# V1_0.net
KiCad netlist of a schematic drawn in EasyEDA Pro
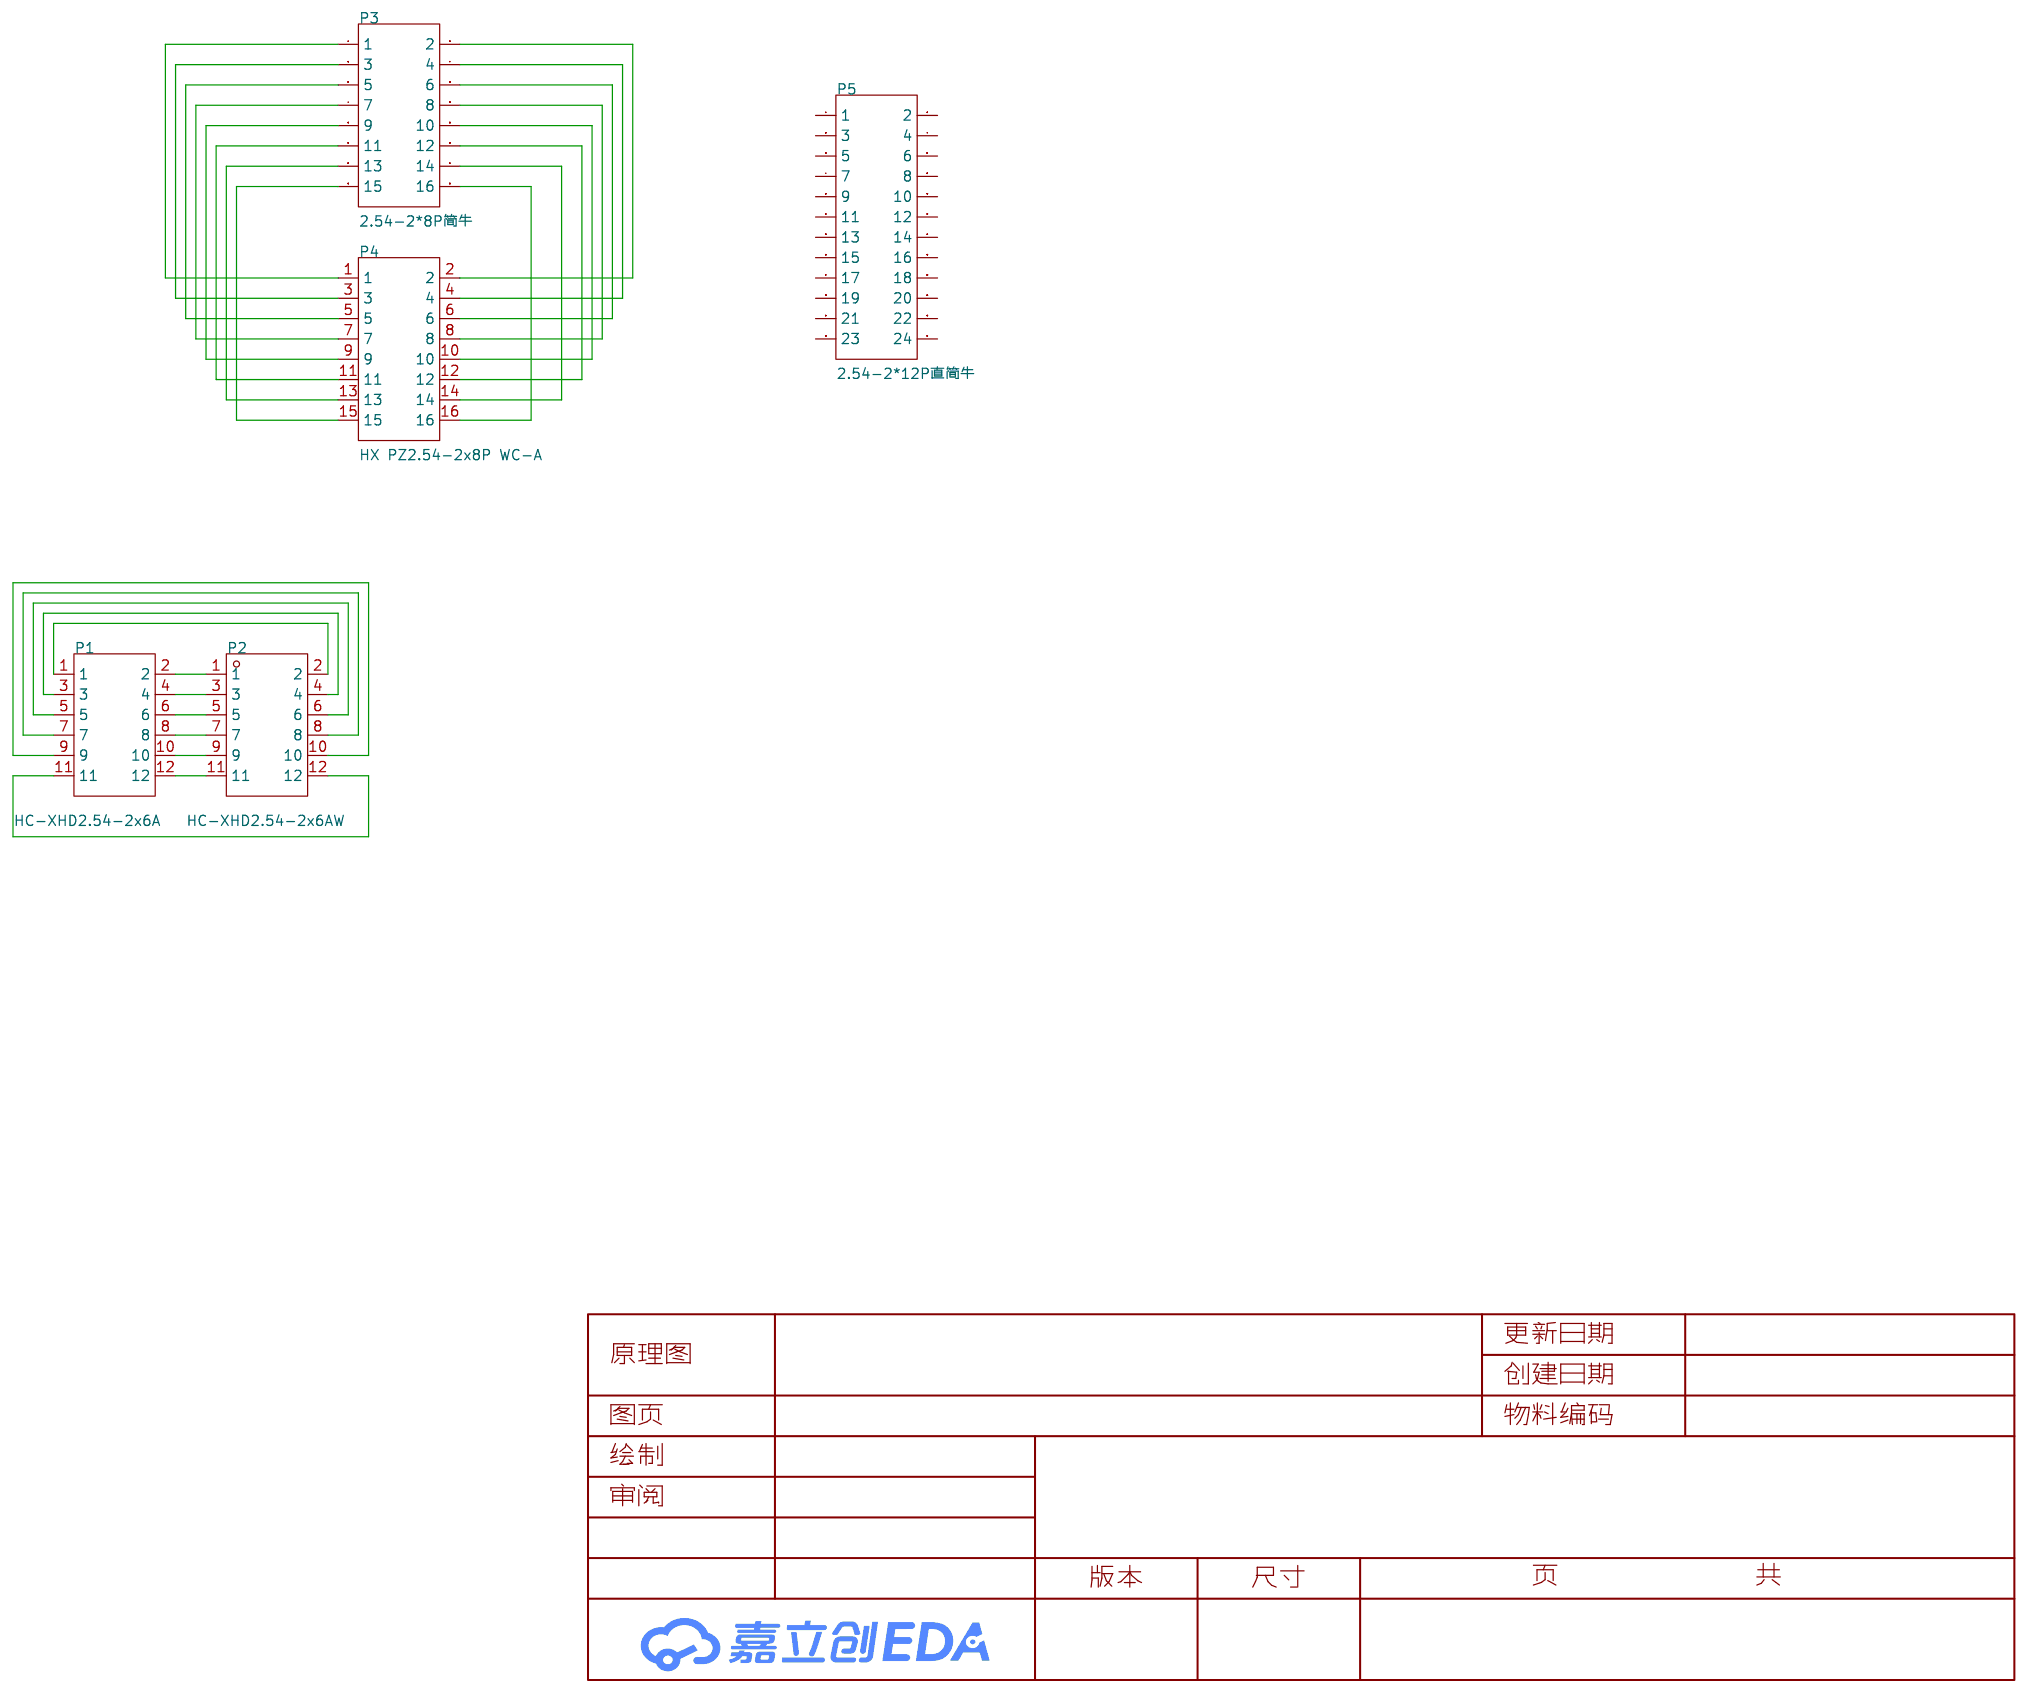
[diagram p0: schematic sheet]

(export (version "E")
  (design (tool "Eeschema 10.0.6"))
  (components
    (comp (ref "P1")
      (value "HC-XHD2.54-2x6A")
      (footprint "easyedapro:CONN-TH_12P-P2.50_HC-XHD2.54-2X6A")
      (fields (field (name "Manufacturer") "HC(虹成电子)"))
      (libsource (lib "easyedapro") (part "HC-XHD2.54-2X6A"))
    )
    (comp (ref "P2")
      (value "HC-XHD2.54-2x6AW")
      (footprint "easyedapro:CONN-TH_12P-P2.50_HC-XHD2.54-2X6AW")
      (fields (field (name "Manufacturer") "HC(虹成电子)"))
      (libsource (lib "easyedapro") (part "HC-XHD2.54-2X6AW"))
    )
    (comp (ref "P3")
      (value "2.54-2*8P简牛")
      (footprint "easyedapro:IDC-TH_16P-P2.54_C3406")
      (description "连接器类型:简牛座;间距:2.54mm;结构:2x8P;安装方式:直插;行距:2.54mm;排数:2;每排PIN数:8;触头材质:-;触头镀层:-;")
      (fields (field (name "Manufacturer") "BOOMELE(博穆精密)"))
      (libsource (lib "easyedapro") (part "HDR-IDC-2.54-2X8P"))
    )
    (comp (ref "P4")
      (value "HX PZ2.54-2x8P WC-A")
      (footprint "easyedapro:HDR-TH_16P-P2.54-H-M-R2-C8-S2.54-W12.9-N")
      (fields (field (name "Manufacturer") "hanxia(韩下)"))
      (libsource (lib "easyedapro") (part "HX PZ2.54-2X8P WC-A"))
    )
    (comp (ref "P5")
      (value "2.54-2*12P直简牛")
      (footprint "easyedapro:IDC-TH_24P-P2.54-V-R2-C12-S2.54")
      (fields (field (name "Manufacturer") "BOOMELE(博穆精密)"))
      (libsource (lib "easyedapro") (part "HDR-IDC-2.54-2X12P"))
    )
  )
  (nets
    (net (code "1") (name "Net-(P1-Pad1)") (class "Default")
      (node (ref "P1") (pin "1") (pinfunction "1_1") (pintype "unspecified"))
      (node (ref "P2") (pin "2") (pinfunction "2_2") (pintype "unspecified"))
    )
    (net (code "2") (name "Net-(P1-Pad2)") (class "Default")
      (node (ref "P1") (pin "2") (pinfunction "2_2") (pintype "unspecified"))
      (node (ref "P2") (pin "1") (pinfunction "1_1") (pintype "unspecified"))
    )
    (net (code "3") (name "Net-(P1-Pad3)") (class "Default")
      (node (ref "P1") (pin "3") (pinfunction "3_3") (pintype "unspecified"))
      (node (ref "P2") (pin "4") (pinfunction "4_4") (pintype "unspecified"))
    )
    (net (code "4") (name "Net-(P1-Pad4)") (class "Default")
      (node (ref "P1") (pin "4") (pinfunction "4_4") (pintype "unspecified"))
      (node (ref "P2") (pin "3") (pinfunction "3_3") (pintype "unspecified"))
    )
    (net (code "5") (name "Net-(P1-Pad5)") (class "Default")
      (node (ref "P1") (pin "5") (pinfunction "5_5") (pintype "unspecified"))
      (node (ref "P2") (pin "6") (pinfunction "6_6") (pintype "unspecified"))
    )
    (net (code "6") (name "Net-(P1-Pad6)") (class "Default")
      (node (ref "P1") (pin "6") (pinfunction "6_6") (pintype "unspecified"))
      (node (ref "P2") (pin "5") (pinfunction "5_5") (pintype "unspecified"))
    )
    (net (code "7") (name "Net-(P1-Pad7)") (class "Default")
      (node (ref "P1") (pin "7") (pinfunction "7_7") (pintype "unspecified"))
      (node (ref "P2") (pin "8") (pinfunction "8_8") (pintype "unspecified"))
    )
    (net (code "8") (name "Net-(P1-Pad8)") (class "Default")
      (node (ref "P1") (pin "8") (pinfunction "8_8") (pintype "unspecified"))
      (node (ref "P2") (pin "7") (pinfunction "7_7") (pintype "unspecified"))
    )
    (net (code "9") (name "Net-(P1-Pad9)") (class "Default")
      (node (ref "P1") (pin "9") (pinfunction "9_9") (pintype "unspecified"))
      (node (ref "P2") (pin "10") (pinfunction "10_10") (pintype "unspecified"))
    )
    (net (code "10") (name "Net-(P1-Pad10)") (class "Default")
      (node (ref "P1") (pin "10") (pinfunction "10_10") (pintype "unspecified"))
      (node (ref "P2") (pin "9") (pinfunction "9_9") (pintype "unspecified"))
    )
    (net (code "11") (name "Net-(P1-Pad11)") (class "Default")
      (node (ref "P1") (pin "11") (pinfunction "11_11") (pintype "unspecified"))
      (node (ref "P2") (pin "12") (pinfunction "12_12") (pintype "unspecified"))
    )
    (net (code "12") (name "Net-(P1-Pad12)") (class "Default")
      (node (ref "P1") (pin "12") (pinfunction "12_12") (pintype "unspecified"))
      (node (ref "P2") (pin "11") (pinfunction "11_11") (pintype "unspecified"))
    )
    (net (code "13") (name "Net-(P3-Pad1)") (class "Default")
      (node (ref "P3") (pin "1") (pinfunction "1_1") (pintype "unspecified"))
      (node (ref "P4") (pin "1") (pinfunction "1_1") (pintype "unspecified"))
    )
    (net (code "14") (name "Net-(P3-Pad2)") (class "Default")
      (node (ref "P3") (pin "2") (pinfunction "2_2") (pintype "unspecified"))
      (node (ref "P4") (pin "2") (pinfunction "2_2") (pintype "unspecified"))
    )
    (net (code "15") (name "Net-(P3-Pad3)") (class "Default")
      (node (ref "P3") (pin "3") (pinfunction "3_3") (pintype "unspecified"))
      (node (ref "P4") (pin "3") (pinfunction "3_3") (pintype "unspecified"))
    )
    (net (code "16") (name "Net-(P3-Pad4)") (class "Default")
      (node (ref "P3") (pin "4") (pinfunction "4_4") (pintype "unspecified"))
      (node (ref "P4") (pin "4") (pinfunction "4_4") (pintype "unspecified"))
    )
    (net (code "17") (name "Net-(P3-Pad5)") (class "Default")
      (node (ref "P3") (pin "5") (pinfunction "5_5") (pintype "unspecified"))
      (node (ref "P4") (pin "5") (pinfunction "5_5") (pintype "unspecified"))
    )
    (net (code "18") (name "Net-(P3-Pad6)") (class "Default")
      (node (ref "P3") (pin "6") (pinfunction "6_6") (pintype "unspecified"))
      (node (ref "P4") (pin "6") (pinfunction "6_6") (pintype "unspecified"))
    )
    (net (code "19") (name "Net-(P3-Pad7)") (class "Default")
      (node (ref "P3") (pin "7") (pinfunction "7_7") (pintype "unspecified"))
      (node (ref "P4") (pin "7") (pinfunction "7_7") (pintype "unspecified"))
    )
    (net (code "20") (name "Net-(P3-Pad8)") (class "Default")
      (node (ref "P3") (pin "8") (pinfunction "8_8") (pintype "unspecified"))
      (node (ref "P4") (pin "8") (pinfunction "8_8") (pintype "unspecified"))
    )
    (net (code "21") (name "Net-(P3-Pad9)") (class "Default")
      (node (ref "P3") (pin "9") (pinfunction "9_9") (pintype "unspecified"))
      (node (ref "P4") (pin "9") (pinfunction "9_9") (pintype "unspecified"))
    )
    (net (code "22") (name "Net-(P3-Pad10)") (class "Default")
      (node (ref "P3") (pin "10") (pinfunction "10_10") (pintype "unspecified"))
      (node (ref "P4") (pin "10") (pinfunction "10_10") (pintype "unspecified"))
    )
    (net (code "23") (name "Net-(P3-Pad11)") (class "Default")
      (node (ref "P3") (pin "11") (pinfunction "11_11") (pintype "unspecified"))
      (node (ref "P4") (pin "11") (pinfunction "11_11") (pintype "unspecified"))
    )
    (net (code "24") (name "Net-(P3-Pad12)") (class "Default")
      (node (ref "P3") (pin "12") (pinfunction "12_12") (pintype "unspecified"))
      (node (ref "P4") (pin "12") (pinfunction "12_12") (pintype "unspecified"))
    )
    (net (code "25") (name "Net-(P3-Pad13)") (class "Default")
      (node (ref "P3") (pin "13") (pinfunction "13_13") (pintype "unspecified"))
      (node (ref "P4") (pin "13") (pinfunction "13_13") (pintype "unspecified"))
    )
    (net (code "26") (name "Net-(P3-Pad14)") (class "Default")
      (node (ref "P3") (pin "14") (pinfunction "14_14") (pintype "unspecified"))
      (node (ref "P4") (pin "14") (pinfunction "14_14") (pintype "unspecified"))
    )
    (net (code "27") (name "Net-(P3-Pad15)") (class "Default")
      (node (ref "P3") (pin "15") (pinfunction "15_15") (pintype "unspecified"))
      (node (ref "P4") (pin "15") (pinfunction "15_15") (pintype "unspecified"))
    )
    (net (code "28") (name "Net-(P3-Pad16)") (class "Default")
      (node (ref "P3") (pin "16") (pinfunction "16_16") (pintype "unspecified"))
      (node (ref "P4") (pin "16") (pinfunction "16_16") (pintype "unspecified"))
    )
    (net (code "29") (name "unconnected-(P5-Pad1)") (class "Default")
      (node (ref "P5") (pin "1") (pinfunction "1_1") (pintype "unspecified"))
    )
    (net (code "30") (name "unconnected-(P5-Pad2)") (class "Default")
      (node (ref "P5") (pin "2") (pinfunction "2_2") (pintype "unspecified"))
    )
    (net (code "31") (name "unconnected-(P5-Pad3)") (class "Default")
      (node (ref "P5") (pin "3") (pinfunction "3_3") (pintype "unspecified"))
    )
    (net (code "32") (name "unconnected-(P5-Pad4)") (class "Default")
      (node (ref "P5") (pin "4") (pinfunction "4_4") (pintype "unspecified"))
    )
    (net (code "33") (name "unconnected-(P5-Pad5)") (class "Default")
      (node (ref "P5") (pin "5") (pinfunction "5_5") (pintype "unspecified"))
    )
    (net (code "34") (name "unconnected-(P5-Pad6)") (class "Default")
      (node (ref "P5") (pin "6") (pinfunction "6_6") (pintype "unspecified"))
    )
    (net (code "35") (name "unconnected-(P5-Pad7)") (class "Default")
      (node (ref "P5") (pin "7") (pinfunction "7_7") (pintype "unspecified"))
    )
    (net (code "36") (name "unconnected-(P5-Pad8)") (class "Default")
      (node (ref "P5") (pin "8") (pinfunction "8_8") (pintype "unspecified"))
    )
    (net (code "37") (name "unconnected-(P5-Pad9)") (class "Default")
      (node (ref "P5") (pin "9") (pinfunction "9_9") (pintype "unspecified"))
    )
    (net (code "38") (name "unconnected-(P5-Pad10)") (class "Default")
      (node (ref "P5") (pin "10") (pinfunction "10_10") (pintype "unspecified"))
    )
    (net (code "39") (name "unconnected-(P5-Pad11)") (class "Default")
      (node (ref "P5") (pin "11") (pinfunction "11_11") (pintype "unspecified"))
    )
    (net (code "40") (name "unconnected-(P5-Pad12)") (class "Default")
      (node (ref "P5") (pin "12") (pinfunction "12_12") (pintype "unspecified"))
    )
    (net (code "41") (name "unconnected-(P5-Pad13)") (class "Default")
      (node (ref "P5") (pin "13") (pinfunction "13_13") (pintype "unspecified"))
    )
    (net (code "42") (name "unconnected-(P5-Pad14)") (class "Default")
      (node (ref "P5") (pin "14") (pinfunction "14_14") (pintype "unspecified"))
    )
    (net (code "43") (name "unconnected-(P5-Pad15)") (class "Default")
      (node (ref "P5") (pin "15") (pinfunction "15_15") (pintype "unspecified"))
    )
    (net (code "44") (name "unconnected-(P5-Pad16)") (class "Default")
      (node (ref "P5") (pin "16") (pinfunction "16_16") (pintype "unspecified"))
    )
    (net (code "45") (name "unconnected-(P5-Pad17)") (class "Default")
      (node (ref "P5") (pin "17") (pinfunction "17_17") (pintype "unspecified"))
    )
    (net (code "46") (name "unconnected-(P5-Pad18)") (class "Default")
      (node (ref "P5") (pin "18") (pinfunction "18_18") (pintype "unspecified"))
    )
    (net (code "47") (name "unconnected-(P5-Pad19)") (class "Default")
      (node (ref "P5") (pin "19") (pinfunction "19_19") (pintype "unspecified"))
    )
    (net (code "48") (name "unconnected-(P5-Pad20)") (class "Default")
      (node (ref "P5") (pin "20") (pinfunction "20_20") (pintype "unspecified"))
    )
    (net (code "49") (name "unconnected-(P5-Pad21)") (class "Default")
      (node (ref "P5") (pin "21") (pinfunction "21_21") (pintype "unspecified"))
    )
    (net (code "50") (name "unconnected-(P5-Pad22)") (class "Default")
      (node (ref "P5") (pin "22") (pinfunction "22_22") (pintype "unspecified"))
    )
    (net (code "51") (name "unconnected-(P5-Pad23)") (class "Default")
      (node (ref "P5") (pin "23") (pinfunction "23_23") (pintype "unspecified"))
    )
    (net (code "52") (name "unconnected-(P5-Pad24)") (class "Default")
      (node (ref "P5") (pin "24") (pinfunction "24_24") (pintype "unspecified"))
    )
  )
)
